# L_SaturationMeter.net
KiCad netlist of a schematic drawn in EAGLE
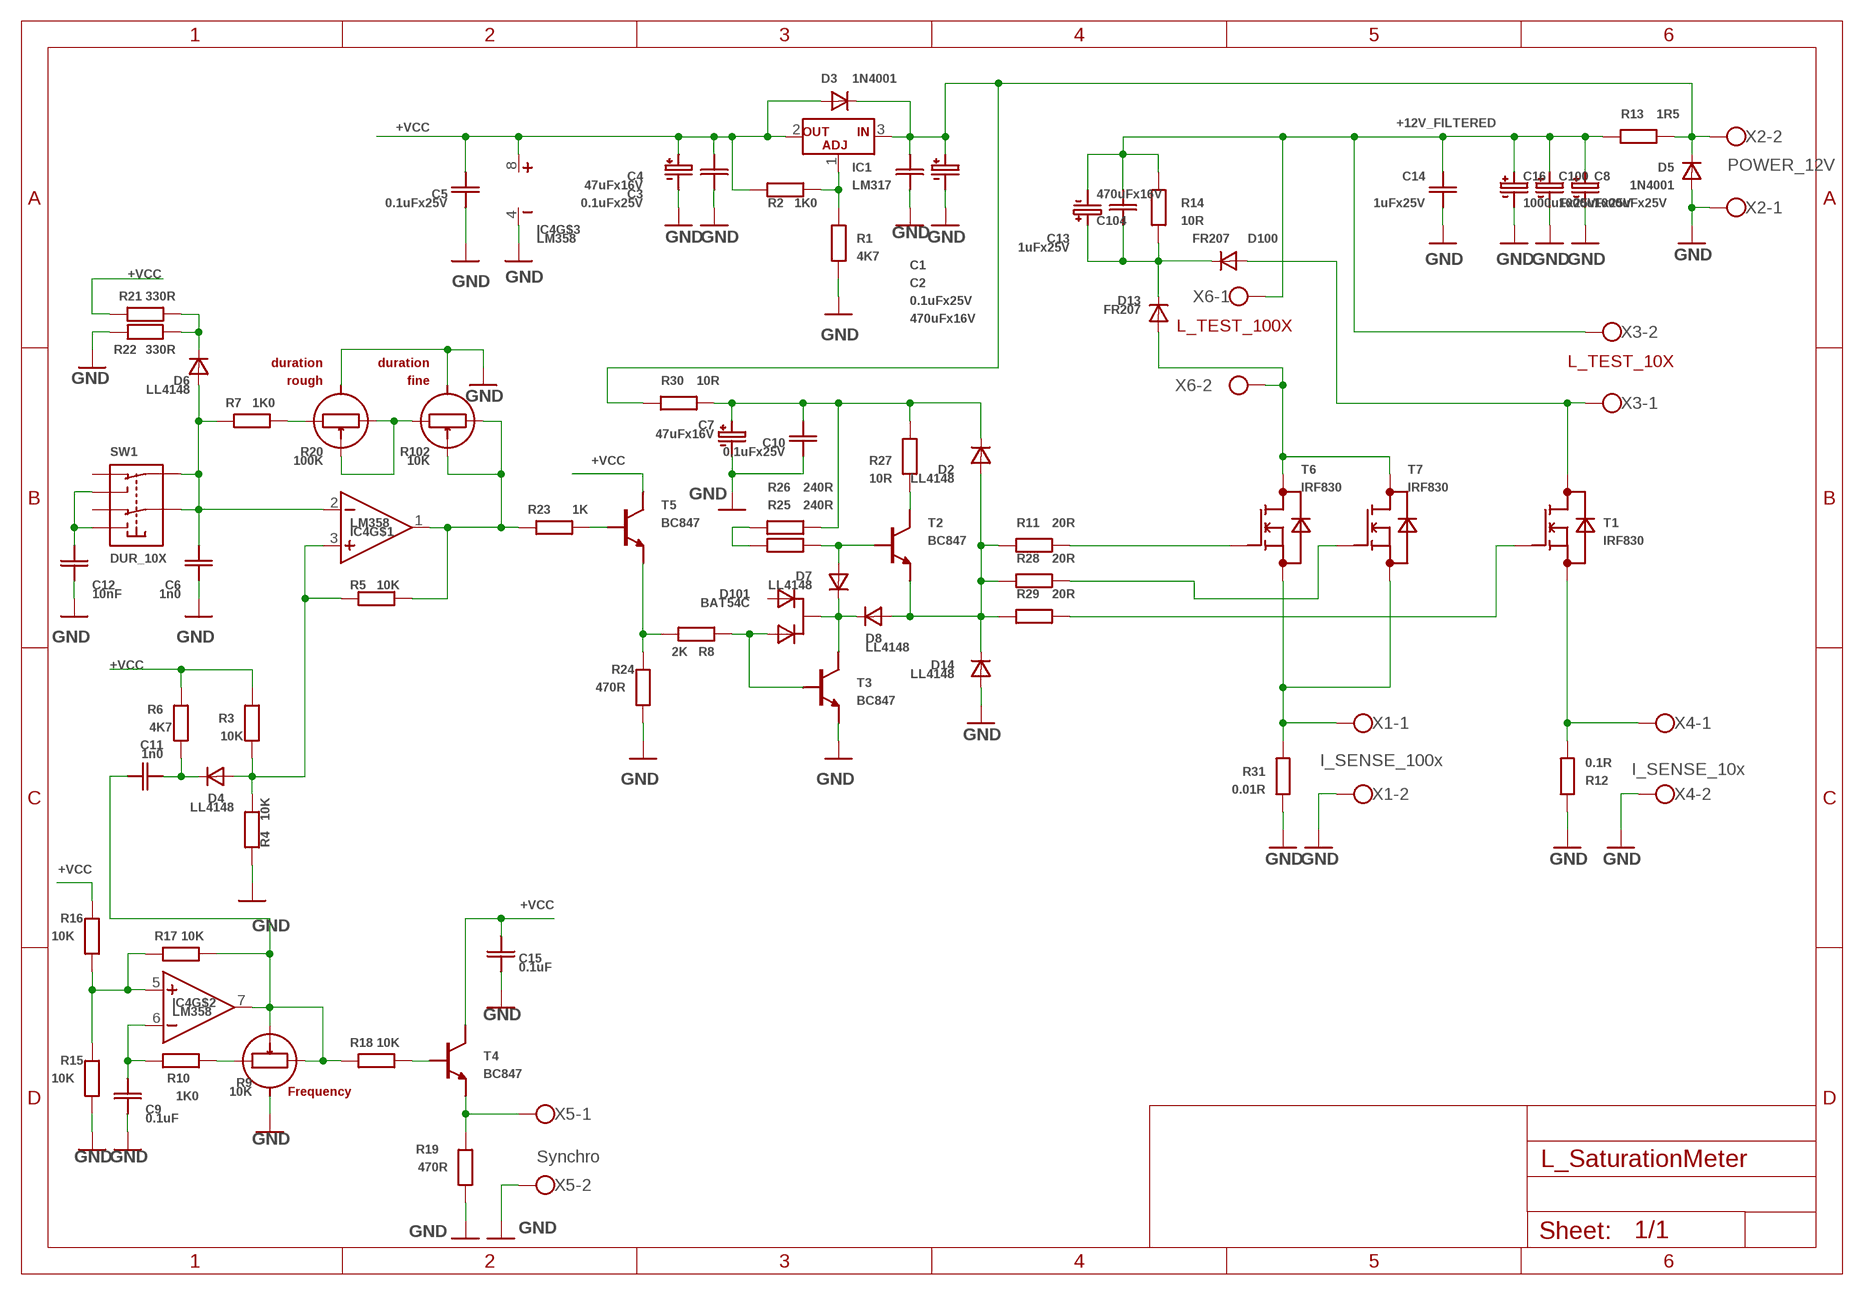
[diagram p0: schematic, sheet 1]

(export (version "E")
  (design (tool "Eeschema 10.0.6"))
  (components
    (comp (ref "C1")
      (value "0.1uFx25V")
      (footprint "eagle-import:RSMD_1206_BIG_GAP")
      (libsource (lib "eagle-import") (part "CSMD_1206_BIG_GAP"))
    )
    (comp (ref "C2")
      (value "470uFx16V")
      (footprint "eagle-import:CE_8.2MM")
      (libsource (lib "eagle-import") (part "CE8.2MM"))
    )
    (comp (ref "C3")
      (value "0.1uFx25V")
      (footprint "eagle-import:RSMD_0805")
      (libsource (lib "eagle-import") (part "CSMD_0805"))
    )
    (comp (ref "C4")
      (value "47uFx16V")
      (footprint "eagle-import:CE_5.2MM")
      (libsource (lib "eagle-import") (part "CE5.2MM"))
    )
    (comp (ref "C5")
      (value "0.1uFx25V")
      (footprint "eagle-import:RSMD_0805")
      (libsource (lib "eagle-import") (part "CSMD_0805"))
    )
    (comp (ref "C6")
      (value "1n0")
      (footprint "eagle-import:RSMD_0805")
      (libsource (lib "eagle-import") (part "CSMD_0805"))
    )
    (comp (ref "C7")
      (value "47uFx16V")
      (footprint "eagle-import:CE_5.2MM")
      (libsource (lib "eagle-import") (part "CE5.2MM"))
    )
    (comp (ref "C8")
      (value "1000uFx25V")
      (footprint "eagle-import:CE_10MM")
      (libsource (lib "eagle-import") (part "CE10MM"))
    )
    (comp (ref "C9")
      (value "0.1uF")
      (footprint "eagle-import:RSMD_0805")
      (libsource (lib "eagle-import") (part "CSMD_0805"))
    )
    (comp (ref "C10")
      (value "0.1uFx25V")
      (footprint "eagle-import:RSMD_0805")
      (libsource (lib "eagle-import") (part "CSMD_0805"))
    )
    (comp (ref "C11")
      (value "1n0")
      (footprint "eagle-import:RSMD_0805")
      (libsource (lib "eagle-import") (part "CSMD_0805"))
    )
    (comp (ref "C12")
      (value "10nF")
      (footprint "eagle-import:RSMD_0805")
      (libsource (lib "eagle-import") (part "CSMD_0805"))
    )
    (comp (ref "C13")
      (value "1uFx25V")
      (footprint "eagle-import:RSMD_1206_BIG_GAP")
      (libsource (lib "eagle-import") (part "CSMD_1206_BIG_GAP"))
    )
    (comp (ref "C14")
      (value "1uFx25V")
      (footprint "eagle-import:RSMD_1206_BIG_GAP")
      (libsource (lib "eagle-import") (part "CSMD_1206_BIG_GAP"))
    )
    (comp (ref "C15")
      (value "0.1uF")
      (footprint "eagle-import:RSMD_0805")
      (libsource (lib "eagle-import") (part "CSMD_0805"))
    )
    (comp (ref "C16")
      (value "1000uFx25V")
      (footprint "eagle-import:CE_10MM")
      (libsource (lib "eagle-import") (part "CE10MM"))
    )
    (comp (ref "C100")
      (value "1000uFx25V")
      (footprint "eagle-import:CE_10MM")
      (libsource (lib "eagle-import") (part "CE10MM"))
    )
    (comp (ref "C104")
      (value "470uFx16V")
      (footprint "eagle-import:CE_8.2MM")
      (libsource (lib "eagle-import") (part "CE8.2MM"))
    )
    (comp (ref "D2")
      (value "LL4148")
      (footprint "eagle-import:SOD-80")
      (libsource (lib "eagle-import") (part "LL4147SOD-80"))
    )
    (comp (ref "D3")
      (value "1N4001")
      (footprint "eagle-import:DO-41_15MM")
      (libsource (lib "eagle-import") (part "1N4001DO-41_15MM"))
    )
    (comp (ref "D4")
      (value "LL4148")
      (footprint "eagle-import:SOD-80")
      (libsource (lib "eagle-import") (part "LL4147SOD-80"))
    )
    (comp (ref "D5")
      (value "1N4001")
      (footprint "eagle-import:DO-41_15MM")
      (libsource (lib "eagle-import") (part "1N4001DO-41_15MM"))
    )
    (comp (ref "D6")
      (value "LL4148")
      (footprint "eagle-import:SOD-80")
      (libsource (lib "eagle-import") (part "LL4147SOD-80"))
    )
    (comp (ref "D7")
      (value "LL4148")
      (footprint "eagle-import:SOD-80")
      (libsource (lib "eagle-import") (part "LL4147SOD-80"))
    )
    (comp (ref "D8")
      (value "LL4148")
      (footprint "eagle-import:SOD-80")
      (libsource (lib "eagle-import") (part "LL4147SOD-80"))
    )
    (comp (ref "D13")
      (value "FR207")
      (footprint "eagle-import:DO-41_5MM")
      (libsource (lib "eagle-import") (part "1N4001DO-41_5MM"))
    )
    (comp (ref "D14")
      (value "LL4148")
      (footprint "eagle-import:SOD-80")
      (libsource (lib "eagle-import") (part "LL4147SOD-80"))
    )
    (comp (ref "D100")
      (value "FR207")
      (footprint "eagle-import:DO-41_20MM")
      (libsource (lib "eagle-import") (part "1N4001DO-41_20MM"))
    )
    (comp (ref "D101")
      (value "BAT54C")
      (footprint "eagle-import:SOT23_SMALL_PADS")
      (libsource (lib "eagle-import") (part "BAT54C(SOT23)"))
    )
    (comp (ref "IC1")
      (value "LM317")
      (footprint "eagle-import:D2PAK")
      (libsource (lib "eagle-import") (part "LM317(D2PAK)"))
    )
    (comp (ref "IC4")
      (value "LM358")
      (footprint "eagle-import:DIP8")
      (libsource (lib "eagle-import") (part "LM358DIP8"))
    )
    (comp (ref "R1")
      (value "4K7")
      (footprint "eagle-import:RSMD_0805")
      (libsource (lib "eagle-import") (part "RSMD_0805"))
    )
    (comp (ref "R2")
      (value "1K0")
      (footprint "eagle-import:RSMD_0805")
      (libsource (lib "eagle-import") (part "RSMD_0805"))
    )
    (comp (ref "R3")
      (value "10K")
      (footprint "eagle-import:RSMD_0805")
      (libsource (lib "eagle-import") (part "RSMD_0805"))
    )
    (comp (ref "R4")
      (value "10K")
      (footprint "eagle-import:RSMD_0805")
      (libsource (lib "eagle-import") (part "RSMD_0805"))
    )
    (comp (ref "R5")
      (value "10K")
      (footprint "eagle-import:RSMD_0805")
      (libsource (lib "eagle-import") (part "RSMD_0805"))
    )
    (comp (ref "R6")
      (value "4K7")
      (footprint "eagle-import:RSMD_0805")
      (libsource (lib "eagle-import") (part "RSMD_0805"))
    )
    (comp (ref "R7")
      (value "1K0")
      (footprint "eagle-import:RSMD_0805")
      (libsource (lib "eagle-import") (part "RSMD_0805"))
    )
    (comp (ref "R8")
      (value "2K")
      (footprint "eagle-import:RSMD_0805")
      (libsource (lib "eagle-import") (part "RSMD_0805"))
    )
    (comp (ref "R9")
      (value "10K")
      (footprint "eagle-import:SP3-4AM")
      (libsource (lib "eagle-import") (part "R_ADJ_WITH_SHIELDSP4-AM"))
    )
    (comp (ref "R10")
      (value "1K0")
      (footprint "eagle-import:RSMD_0805")
      (libsource (lib "eagle-import") (part "RSMD_0805"))
    )
    (comp (ref "R11")
      (value "20R")
      (footprint "eagle-import:RSMD_0805")
      (libsource (lib "eagle-import") (part "RSMD_0805"))
    )
    (comp (ref "R12")
      (value "0.1R")
      (footprint "eagle-import:R_1.0W_VERTICAL")
      (libsource (lib "eagle-import") (part "R1.0W_VERT"))
    )
    (comp (ref "R13")
      (value "1R5")
      (footprint "eagle-import:R_2.0W")
      (libsource (lib "eagle-import") (part "R2.0W"))
    )
    (comp (ref "R14")
      (value "10R")
      (footprint "eagle-import:R_1.0W_VERTICAL")
      (libsource (lib "eagle-import") (part "R1.0W_VERT"))
    )
    (comp (ref "R15")
      (value "10K")
      (footprint "eagle-import:RSMD_0805")
      (libsource (lib "eagle-import") (part "RSMD_0805"))
    )
    (comp (ref "R16")
      (value "10K")
      (footprint "eagle-import:RSMD_0805")
      (libsource (lib "eagle-import") (part "RSMD_0805"))
    )
    (comp (ref "R17")
      (value "10K")
      (footprint "eagle-import:RSMD_0805")
      (libsource (lib "eagle-import") (part "RSMD_0805"))
    )
    (comp (ref "R18")
      (value "10K")
      (footprint "eagle-import:RSMD_0805")
      (libsource (lib "eagle-import") (part "RSMD_0805"))
    )
    (comp (ref "R19")
      (value "470R")
      (footprint "eagle-import:RSMD_1206_BIG_GAP")
      (libsource (lib "eagle-import") (part "RSMD_1206_BIG_GAP"))
    )
    (comp (ref "R20")
      (value "100K")
      (footprint "eagle-import:SP3-4AM")
      (libsource (lib "eagle-import") (part "R_ADJ_WITH_SHIELDSP4-AM"))
    )
    (comp (ref "R21")
      (value "330R")
      (footprint "eagle-import:RSMD_0805")
      (libsource (lib "eagle-import") (part "RSMD_0805"))
    )
    (comp (ref "R22")
      (value "330R")
      (footprint "eagle-import:RSMD_0805")
      (libsource (lib "eagle-import") (part "RSMD_0805"))
    )
    (comp (ref "R23")
      (value "1K")
      (footprint "eagle-import:RSMD_1206_BIG_GAP")
      (libsource (lib "eagle-import") (part "RSMD_1206_BIG_GAP"))
    )
    (comp (ref "R24")
      (value "470R")
      (footprint "eagle-import:RSMD_1206_BIG_GAP")
      (libsource (lib "eagle-import") (part "RSMD_1206_BIG_GAP"))
    )
    (comp (ref "R25")
      (value "240R")
      (footprint "eagle-import:RSMD_1206_BIG_GAP")
      (libsource (lib "eagle-import") (part "RSMD_1206_BIG_GAP"))
    )
    (comp (ref "R26")
      (value "240R")
      (footprint "eagle-import:RSMD_1206_BIG_GAP")
      (libsource (lib "eagle-import") (part "RSMD_1206_BIG_GAP"))
    )
    (comp (ref "R27")
      (value "10R")
      (footprint "eagle-import:RSMD_1206_BIG_GAP")
      (libsource (lib "eagle-import") (part "RSMD_1206_BIG_GAP"))
    )
    (comp (ref "R28")
      (value "20R")
      (footprint "eagle-import:RSMD_0805")
      (libsource (lib "eagle-import") (part "RSMD_0805"))
    )
    (comp (ref "R29")
      (value "20R")
      (footprint "eagle-import:RSMD_0805")
      (libsource (lib "eagle-import") (part "RSMD_0805"))
    )
    (comp (ref "R30")
      (value "10R")
      (footprint "eagle-import:R_0.5W")
      (libsource (lib "eagle-import") (part "R0.5W"))
    )
    (comp (ref "R31")
      (value "0.01R")
      (footprint "eagle-import:RSMD_2512")
      (libsource (lib "eagle-import") (part "RSMD_2512"))
    )
    (comp (ref "R102")
      (value "10K")
      (footprint "eagle-import:SP3-4AM")
      (libsource (lib "eagle-import") (part "R_ADJ_WITH_SHIELDSP4-AM"))
    )
    (comp (ref "SW1")
      (value "DUR_10X")
      (footprint "eagle-import:SWITCH_DOUBLE_2.54X4.0MM")
      (libsource (lib "eagle-import") (part "SWITCH_DOUBLE(2.54X4MM)"))
    )
    (comp (ref "T1")
      (value "IRF830")
      (footprint "eagle-import:D2PAK")
      (libsource (lib "eagle-import") (part "IRF830D2PAK"))
    )
    (comp (ref "T2")
      (value "BC847")
      (footprint "eagle-import:SOT23_SMALL_PADS")
      (libsource (lib "eagle-import") (part "BC847SOT23_SMALL_PADS"))
    )
    (comp (ref "T3")
      (value "BC847")
      (footprint "eagle-import:SOT23_SMALL_PADS")
      (libsource (lib "eagle-import") (part "BC847SOT23_SMALL_PADS"))
    )
    (comp (ref "T4")
      (value "BC847")
      (footprint "eagle-import:SOT23_SMALL_PADS")
      (libsource (lib "eagle-import") (part "BC847SOT23_SMALL_PADS"))
    )
    (comp (ref "T5")
      (value "BC847")
      (footprint "eagle-import:SOT23_SMALL_PADS")
      (libsource (lib "eagle-import") (part "BC847SOT23_SMALL_PADS"))
    )
    (comp (ref "T6")
      (value "IRF830")
      (footprint "eagle-import:D2PAK")
      (libsource (lib "eagle-import") (part "IRF830D2PAK"))
    )
    (comp (ref "T7")
      (value "IRF830")
      (footprint "eagle-import:D2PAK")
      (libsource (lib "eagle-import") (part "IRF830D2PAK"))
    )
    (comp (ref "X1")
      (value "I_SENSE_100x")
      (footprint "eagle-import:W237-102")
      (fields
        (field (name "MPN") "237-102")
        (field (name "MPN_1") "237-102")
        (field (name "OC_FARNELL") "unknown")
        (field (name "OC_NEWARK") "70K9898")
      )
      (libsource (lib "eagle-import") (part "W237-102"))
    )
    (comp (ref "X2")
      (value "POWER_12V")
      (footprint "eagle-import:W237-102")
      (fields (field (name "MPN") "237-102"))
      (libsource (lib "eagle-import") (part "W237-102"))
    )
    (comp (ref "X3")
      (value "L_TEST_END")
      (footprint "eagle-import:W237-102")
      (fields (field (name "MPN") "237-102"))
      (libsource (lib "eagle-import") (part "W237-102"))
    )
    (comp (ref "X4")
      (value "I_SENSE_10x")
      (footprint "eagle-import:W237-102")
      (fields (field (name "MPN") "237-102"))
      (libsource (lib "eagle-import") (part "W237-102"))
    )
    (comp (ref "X5")
      (value "Synchro")
      (footprint "eagle-import:W237-102")
      (fields
        (field (name "MPN") "237-102")
        (field (name "MPN_1") "237-102")
        (field (name "OC_FARNELL") "unknown")
        (field (name "OC_NEWARK") "70K9898")
      )
      (libsource (lib "eagle-import") (part "W237-102"))
    )
    (comp (ref "X6")
      (value "L_TEST_END")
      (footprint "eagle-import:W237-102")
      (fields
        (field (name "MPN") "237-102")
        (field (name "MPN_1") "237-102")
        (field (name "OC_FARNELL") "unknown")
        (field (name "OC_NEWARK") "70K9898")
      )
      (libsource (lib "eagle-import") (part "W237-102"))
    )
  )
  (nets
    (net (code "1") (name "/+12V_FILTERED") (class "Default")
      (node (ref "C100") (pin "PLUS") (pinfunction "PLUS_PLUS") (pintype "bidirectional"))
      (node (ref "C104") (pin "MINUS") (pinfunction "MINUS_MINUS") (pintype "bidirectional"))
      (node (ref "C13") (pin "PAD_0") (pinfunction "PIN0_PAD_0") (pintype "bidirectional"))
      (node (ref "C14") (pin "PAD_0") (pinfunction "PIN0_PAD_0") (pintype "bidirectional"))
      (node (ref "C16") (pin "PLUS") (pinfunction "PLUS_PLUS") (pintype "bidirectional"))
      (node (ref "C8") (pin "PLUS") (pinfunction "PLUS_PLUS") (pintype "bidirectional"))
      (node (ref "R13") (pin "PAD1") (pinfunction "PIN1_PAD1") (pintype "passive"))
      (node (ref "R14") (pin "PAD1") (pinfunction "PIN1_PAD1") (pintype "passive"))
      (node (ref "X3") (pin "2") (pinfunction "KL_2") (pintype "passive"))
      (node (ref "X6") (pin "1") (pinfunction "KL_1") (pintype "passive"))
    )
    (net (code "2") (name "/+VCC") (class "Default")
      (node (ref "C15") (pin "PAD_0") (pinfunction "PIN0_PAD_0") (pintype "bidirectional"))
      (node (ref "C3") (pin "PAD_0") (pinfunction "PIN0_PAD_0") (pintype "bidirectional"))
      (node (ref "C4") (pin "PLUS") (pinfunction "PLUS_PLUS") (pintype "bidirectional"))
      (node (ref "C5") (pin "PAD_0") (pinfunction "PIN0_PAD_0") (pintype "bidirectional"))
      (node (ref "D3") (pin "ANODE") (pinfunction "ANODE_ANODE") (pintype "passive"))
      (node (ref "IC1") (pin "2") (pinfunction "OUT_2") (pintype "output"))
      (node (ref "IC4") (pin "8") (pinfunction "VCC_8") (pintype "power_in"))
      (node (ref "R16") (pin "PAD_1") (pinfunction "PIN1_PAD_1") (pintype "passive"))
      (node (ref "R2") (pin "PAD_1") (pinfunction "PIN1_PAD_1") (pintype "passive"))
      (node (ref "R21") (pin "PAD_1") (pinfunction "PIN1_PAD_1") (pintype "passive"))
      (node (ref "R3") (pin "PAD_1") (pinfunction "PIN1_PAD_1") (pintype "passive"))
      (node (ref "R6") (pin "PAD_0") (pinfunction "PIN0_PAD_0") (pintype "passive"))
      (node (ref "T4") (pin "3") (pinfunction "C_3") (pintype "bidirectional"))
      (node (ref "T5") (pin "3") (pinfunction "C_3") (pintype "bidirectional"))
    )
    (net (code "3") (name "GND") (class "Default")
      (node (ref "C1") (pin "PAD_1") (pinfunction "PIN1_PAD_1") (pintype "bidirectional"))
      (node (ref "C10") (pin "PAD_1") (pinfunction "PIN1_PAD_1") (pintype "bidirectional"))
      (node (ref "C100") (pin "MINUS") (pinfunction "MINUS_MINUS") (pintype "bidirectional"))
      (node (ref "C12") (pin "PAD_1") (pinfunction "PIN1_PAD_1") (pintype "bidirectional"))
      (node (ref "C14") (pin "PAD_1") (pinfunction "PIN1_PAD_1") (pintype "bidirectional"))
      (node (ref "C15") (pin "PAD_1") (pinfunction "PIN1_PAD_1") (pintype "bidirectional"))
      (node (ref "C16") (pin "MINUS") (pinfunction "MINUS_MINUS") (pintype "bidirectional"))
      (node (ref "C2") (pin "MINUS") (pinfunction "MINUS_MINUS") (pintype "bidirectional"))
      (node (ref "C3") (pin "PAD_1") (pinfunction "PIN1_PAD_1") (pintype "bidirectional"))
      (node (ref "C4") (pin "MINUS") (pinfunction "MINUS_MINUS") (pintype "bidirectional"))
      (node (ref "C5") (pin "PAD_1") (pinfunction "PIN1_PAD_1") (pintype "bidirectional"))
      (node (ref "C6") (pin "PAD_1") (pinfunction "PIN1_PAD_1") (pintype "bidirectional"))
      (node (ref "C7") (pin "MINUS") (pinfunction "MINUS_MINUS") (pintype "bidirectional"))
      (node (ref "C8") (pin "MINUS") (pinfunction "MINUS_MINUS") (pintype "bidirectional"))
      (node (ref "C9") (pin "PAD_1") (pinfunction "PIN1_PAD_1") (pintype "bidirectional"))
      (node (ref "D14") (pin "ANODE") (pinfunction "ANODE_ANODE") (pintype "passive"))
      (node (ref "D5") (pin "ANODE") (pinfunction "ANODE_ANODE") (pintype "passive"))
      (node (ref "IC4") (pin "4") (pinfunction "GND_4") (pintype "power_in"))
      (node (ref "R1") (pin "PAD_0") (pinfunction "PIN0_PAD_0") (pintype "passive"))
      (node (ref "R102") (pin "PACKAGE1") (pinfunction "PACKAGE_PACKAGE1") (pintype "bidirectional"))
      (node (ref "R102") (pin "PACKAGE2") (pinfunction "PACKAGE_PACKAGE2") (pintype "bidirectional"))
      (node (ref "R12") (pin "PAD1") (pinfunction "PIN1_PAD1") (pintype "passive"))
      (node (ref "R15") (pin "PAD_0") (pinfunction "PIN0_PAD_0") (pintype "passive"))
      (node (ref "R19") (pin "PAD_1") (pinfunction "PIN1_PAD_1") (pintype "passive"))
      (node (ref "R20") (pin "PACKAGE1") (pinfunction "PACKAGE_PACKAGE1") (pintype "bidirectional"))
      (node (ref "R20") (pin "PACKAGE2") (pinfunction "PACKAGE_PACKAGE2") (pintype "bidirectional"))
      (node (ref "R22") (pin "PAD_0") (pinfunction "PIN0_PAD_0") (pintype "passive"))
      (node (ref "R24") (pin "PAD_1") (pinfunction "PIN1_PAD_1") (pintype "passive"))
      (node (ref "R31") (pin "PAD0") (pinfunction "PIN0_PAD0") (pintype "passive"))
      (node (ref "R4") (pin "PAD_1") (pinfunction "PIN1_PAD_1") (pintype "passive"))
      (node (ref "R9") (pin "PACKAGE1") (pinfunction "PACKAGE_PACKAGE1") (pintype "bidirectional"))
      (node (ref "R9") (pin "PACKAGE2") (pinfunction "PACKAGE_PACKAGE2") (pintype "bidirectional"))
      (node (ref "T3") (pin "2") (pinfunction "E_2") (pintype "bidirectional"))
      (node (ref "X1") (pin "2") (pinfunction "KL_2") (pintype "passive"))
      (node (ref "X2") (pin "1") (pinfunction "KL_1") (pintype "passive"))
      (node (ref "X4") (pin "2") (pinfunction "KL_2") (pintype "passive"))
      (node (ref "X5") (pin "2") (pinfunction "KL_2") (pintype "passive"))
    )
    (net (code "4") (name "Net-(C1-PIN0)") (class "Default")
      (node (ref "C1") (pin "PAD_0") (pinfunction "PIN0_PAD_0") (pintype "bidirectional"))
      (node (ref "C2") (pin "PLUS") (pinfunction "PLUS_PLUS") (pintype "bidirectional"))
      (node (ref "D3") (pin "CATHODE") (pinfunction "CATHODE_CATHODE") (pintype "passive"))
      (node (ref "D5") (pin "CATHODE") (pinfunction "CATHODE_CATHODE") (pintype "passive"))
      (node (ref "IC1") (pin "3") (pinfunction "IN_3") (pintype "input"))
      (node (ref "R13") (pin "PAD_0") (pinfunction "PIN0_PAD_0") (pintype "passive"))
      (node (ref "R30") (pin "PAD1") (pinfunction "PIN1_PAD1") (pintype "passive"))
      (node (ref "X2") (pin "2") (pinfunction "KL_2") (pintype "passive"))
    )
    (net (code "5") (name "Net-(C6-PIN0)") (class "Default")
      (node (ref "C6") (pin "PAD_0") (pinfunction "PIN0_PAD_0") (pintype "bidirectional"))
      (node (ref "D6") (pin "ANODE") (pinfunction "ANODE_ANODE") (pintype "passive"))
      (node (ref "IC4") (pin "2") (pinfunction "IN-_2") (pintype "input"))
      (node (ref "R7") (pin "PAD_1") (pinfunction "PIN1_PAD_1") (pintype "passive"))
      (node (ref "SW1") (pin "CENTER1") (pinfunction "CENTER1_CENTER1") (pintype "bidirectional"))
      (node (ref "SW1") (pin "CENTER2") (pinfunction "CENTER2_CENTER2") (pintype "bidirectional"))
    )
    (net (code "6") (name "Net-(C9-PIN0)") (class "Default")
      (node (ref "C9") (pin "PAD_0") (pinfunction "PIN0_PAD_0") (pintype "bidirectional"))
      (node (ref "IC4") (pin "6") (pinfunction "IN-_6") (pintype "input"))
      (node (ref "R10") (pin "PAD_0") (pinfunction "PIN0_PAD_0") (pintype "passive"))
    )
    (net (code "7") (name "Net-(C10-PIN0)") (class "Default")
      (node (ref "C10") (pin "PAD_0") (pinfunction "PIN0_PAD_0") (pintype "bidirectional"))
      (node (ref "C7") (pin "PLUS") (pinfunction "PLUS_PLUS") (pintype "bidirectional"))
      (node (ref "D2") (pin "CATHODE") (pinfunction "CATHODE_CATHODE") (pintype "passive"))
      (node (ref "R26") (pin "PAD_0") (pinfunction "PIN0_PAD_0") (pintype "passive"))
      (node (ref "R27") (pin "PAD_0") (pinfunction "PIN0_PAD_0") (pintype "passive"))
      (node (ref "R30") (pin "PAD_0") (pinfunction "PIN0_PAD_0") (pintype "passive"))
    )
    (net (code "8") (name "Net-(C11-PIN0)") (class "Default")
      (node (ref "C11") (pin "PAD_0") (pinfunction "PIN0_PAD_0") (pintype "bidirectional"))
      (node (ref "D4") (pin "CATHODE") (pinfunction "CATHODE_CATHODE") (pintype "passive"))
      (node (ref "R6") (pin "PAD_1") (pinfunction "PIN1_PAD_1") (pintype "passive"))
    )
    (net (code "9") (name "Net-(C11-PIN1)") (class "Default")
      (node (ref "C11") (pin "PAD_1") (pinfunction "PIN1_PAD_1") (pintype "bidirectional"))
      (node (ref "IC4") (pin "7") (pinfunction "OUT_7") (pintype "output"))
      (node (ref "R17") (pin "PAD_0") (pinfunction "PIN0_PAD_0") (pintype "passive"))
      (node (ref "R18") (pin "PAD_1") (pinfunction "PIN1_PAD_1") (pintype "passive"))
      (node (ref "R9") (pin "END_B") (pinfunction "END_B_END_B") (pintype "passive"))
      (node (ref "R9") (pin "MIDDLE") (pinfunction "MIDDLE_MIDDLE") (pintype "passive"))
    )
    (net (code "10") (name "Net-(C12-PIN0)") (class "Default")
      (node (ref "C12") (pin "PAD_0") (pinfunction "PIN0_PAD_0") (pintype "bidirectional"))
      (node (ref "SW1") (pin "POS_A1") (pinfunction "POS_A1_POS_A1") (pintype "bidirectional"))
      (node (ref "SW1") (pin "POS_A2") (pinfunction "POS_A2_POS_A2") (pintype "bidirectional"))
    )
    (net (code "11") (name "Net-(C13-PIN1)") (class "Default")
      (node (ref "C104") (pin "PLUS") (pinfunction "PLUS_PLUS") (pintype "bidirectional"))
      (node (ref "C13") (pin "PAD_1") (pinfunction "PIN1_PAD_1") (pintype "bidirectional"))
      (node (ref "D100") (pin "CATHODE") (pinfunction "CATHODE_CATHODE") (pintype "passive"))
      (node (ref "D13") (pin "CATHODE") (pinfunction "CATHODE_CATHODE") (pintype "passive"))
      (node (ref "R14") (pin "PAD_0") (pinfunction "PIN0_PAD_0") (pintype "passive"))
    )
    (net (code "12") (name "Net-(D101-ANODE2)") (class "Default")
      (node (ref "D101") (pin "2") (pinfunction "ANODE2_2") (pintype "passive"))
      (node (ref "R8") (pin "PAD_1") (pinfunction "PIN1_PAD_1") (pintype "passive"))
      (node (ref "T3") (pin "1") (pinfunction "B_1") (pintype "bidirectional"))
    )
    (net (code "13") (name "Net-(D101-CATHODE)") (class "Default")
      (node (ref "D101") (pin "3") (pinfunction "CATHODE_3") (pintype "passive"))
      (node (ref "D7") (pin "CATHODE") (pinfunction "CATHODE_CATHODE") (pintype "passive"))
      (node (ref "D8") (pin "CATHODE") (pinfunction "CATHODE_CATHODE") (pintype "passive"))
      (node (ref "T3") (pin "3") (pinfunction "C_3") (pintype "bidirectional"))
    )
    (net (code "14") (name "Net-(IC1-ADJ)") (class "Default")
      (node (ref "IC1") (pin "1") (pinfunction "ADJ_1") (pintype "input"))
      (node (ref "R1") (pin "PAD_1") (pinfunction "PIN1_PAD_1") (pintype "passive"))
      (node (ref "R2") (pin "PAD_0") (pinfunction "PIN0_PAD_0") (pintype "passive"))
    )
    (net (code "15") (name "Net-(IC4A-IN+)") (class "Default")
      (node (ref "D4") (pin "ANODE") (pinfunction "ANODE_ANODE") (pintype "passive"))
      (node (ref "IC4") (pin "3") (pinfunction "IN+_3") (pintype "input"))
      (node (ref "R3") (pin "PAD_0") (pinfunction "PIN0_PAD_0") (pintype "passive"))
      (node (ref "R4") (pin "PAD_0") (pinfunction "PIN0_PAD_0") (pintype "passive"))
      (node (ref "R5") (pin "PAD_1") (pinfunction "PIN1_PAD_1") (pintype "passive"))
    )
    (net (code "16") (name "Net-(IC4A-OUT)") (class "Default")
      (node (ref "IC4") (pin "1") (pinfunction "OUT_1") (pintype "output"))
      (node (ref "R102") (pin "END_B") (pinfunction "END_B_END_B") (pintype "passive"))
      (node (ref "R102") (pin "MIDDLE") (pinfunction "MIDDLE_MIDDLE") (pintype "passive"))
      (node (ref "R23") (pin "PAD_1") (pinfunction "PIN1_PAD_1") (pintype "passive"))
      (node (ref "R5") (pin "PAD_0") (pinfunction "PIN0_PAD_0") (pintype "passive"))
    )
    (net (code "17") (name "Net-(IC4B-IN+)") (class "Default")
      (node (ref "IC4") (pin "5") (pinfunction "IN+_5") (pintype "input"))
      (node (ref "R15") (pin "PAD_1") (pinfunction "PIN1_PAD_1") (pintype "passive"))
      (node (ref "R16") (pin "PAD_0") (pinfunction "PIN0_PAD_0") (pintype "passive"))
      (node (ref "R17") (pin "PAD_1") (pinfunction "PIN1_PAD_1") (pintype "passive"))
    )
    (net (code "18") (name "Net-(R7-PIN0)") (class "Default")
      (node (ref "R20") (pin "END_A") (pinfunction "END_A_END_A") (pintype "passive"))
      (node (ref "R7") (pin "PAD_0") (pinfunction "PIN0_PAD_0") (pintype "passive"))
    )
    (net (code "19") (name "Net-(R10-PIN1)") (class "Default")
      (node (ref "R10") (pin "PAD_1") (pinfunction "PIN1_PAD_1") (pintype "passive"))
      (node (ref "R9") (pin "END_A") (pinfunction "END_A_END_A") (pintype "passive"))
    )
    (net (code "20") (name "Net-(R11-PIN0)") (class "Default")
      (node (ref "D14") (pin "CATHODE") (pinfunction "CATHODE_CATHODE") (pintype "passive"))
      (node (ref "D2") (pin "ANODE") (pinfunction "ANODE_ANODE") (pintype "passive"))
      (node (ref "D8") (pin "ANODE") (pinfunction "ANODE_ANODE") (pintype "passive"))
      (node (ref "R11") (pin "PAD_0") (pinfunction "PIN0_PAD_0") (pintype "passive"))
      (node (ref "R28") (pin "PAD_0") (pinfunction "PIN0_PAD_0") (pintype "passive"))
      (node (ref "R29") (pin "PAD_0") (pinfunction "PIN0_PAD_0") (pintype "passive"))
      (node (ref "T2") (pin "2") (pinfunction "E_2") (pintype "bidirectional"))
    )
    (net (code "21") (name "Net-(R11-PIN1)") (class "Default")
      (node (ref "R11") (pin "PAD_1") (pinfunction "PIN1_PAD_1") (pintype "passive"))
      (node (ref "T6") (pin "1") (pinfunction "GATE_1") (pintype "bidirectional"))
    )
    (net (code "22") (name "Net-(R12-PIN0)") (class "Default")
      (node (ref "R12") (pin "PAD_0") (pinfunction "PIN0_PAD_0") (pintype "passive"))
      (node (ref "T1") (pin "3") (pinfunction "SOURCE_3") (pintype "bidirectional"))
      (node (ref "X4") (pin "1") (pinfunction "KL_1") (pintype "passive"))
    )
    (net (code "23") (name "Net-(R18-PIN0)") (class "Default")
      (node (ref "R18") (pin "PAD_0") (pinfunction "PIN0_PAD_0") (pintype "passive"))
      (node (ref "T4") (pin "1") (pinfunction "B_1") (pintype "bidirectional"))
    )
    (net (code "24") (name "Net-(R19-PIN0)") (class "Default")
      (node (ref "R19") (pin "PAD_0") (pinfunction "PIN0_PAD_0") (pintype "passive"))
      (node (ref "T4") (pin "2") (pinfunction "E_2") (pintype "bidirectional"))
      (node (ref "X5") (pin "1") (pinfunction "KL_1") (pintype "passive"))
    )
    (net (code "25") (name "Net-(R21-PIN0)") (class "Default")
      (node (ref "D6") (pin "CATHODE") (pinfunction "CATHODE_CATHODE") (pintype "passive"))
      (node (ref "R21") (pin "PAD_0") (pinfunction "PIN0_PAD_0") (pintype "passive"))
      (node (ref "R22") (pin "PAD_1") (pinfunction "PIN1_PAD_1") (pintype "passive"))
    )
    (net (code "26") (name "Net-(R23-PIN0)") (class "Default")
      (node (ref "R23") (pin "PAD_0") (pinfunction "PIN0_PAD_0") (pintype "passive"))
      (node (ref "T5") (pin "1") (pinfunction "B_1") (pintype "bidirectional"))
    )
    (net (code "27") (name "Net-(R24-PIN0)") (class "Default")
      (node (ref "R24") (pin "PAD_0") (pinfunction "PIN0_PAD_0") (pintype "passive"))
      (node (ref "R8") (pin "PAD_0") (pinfunction "PIN0_PAD_0") (pintype "passive"))
      (node (ref "T5") (pin "2") (pinfunction "E_2") (pintype "bidirectional"))
    )
    (net (code "28") (name "Net-(R25-PIN0)") (class "Default")
      (node (ref "R25") (pin "PAD_0") (pinfunction "PIN0_PAD_0") (pintype "passive"))
      (node (ref "R26") (pin "PAD_1") (pinfunction "PIN1_PAD_1") (pintype "passive"))
    )
    (net (code "29") (name "Net-(R25-PIN1)") (class "Default")
      (node (ref "D7") (pin "ANODE") (pinfunction "ANODE_ANODE") (pintype "passive"))
      (node (ref "R25") (pin "PAD_1") (pinfunction "PIN1_PAD_1") (pintype "passive"))
      (node (ref "T2") (pin "1") (pinfunction "B_1") (pintype "bidirectional"))
    )
    (net (code "30") (name "Net-(R27-PIN1)") (class "Default")
      (node (ref "R27") (pin "PAD_1") (pinfunction "PIN1_PAD_1") (pintype "passive"))
      (node (ref "T2") (pin "3") (pinfunction "C_3") (pintype "bidirectional"))
    )
    (net (code "31") (name "Net-(R28-PIN1)") (class "Default")
      (node (ref "R28") (pin "PAD_1") (pinfunction "PIN1_PAD_1") (pintype "passive"))
      (node (ref "T7") (pin "1") (pinfunction "GATE_1") (pintype "bidirectional"))
    )
    (net (code "32") (name "Net-(R29-PIN1)") (class "Default")
      (node (ref "R29") (pin "PAD_1") (pinfunction "PIN1_PAD_1") (pintype "passive"))
      (node (ref "T1") (pin "1") (pinfunction "GATE_1") (pintype "bidirectional"))
    )
    (net (code "33") (name "Net-(R31-PIN1)") (class "Default")
      (node (ref "R31") (pin "PAD1") (pinfunction "PIN1_PAD1") (pintype "passive"))
      (node (ref "T6") (pin "3") (pinfunction "SOURCE_3") (pintype "bidirectional"))
      (node (ref "T7") (pin "3") (pinfunction "SOURCE_3") (pintype "bidirectional"))
      (node (ref "X1") (pin "1") (pinfunction "KL_1") (pintype "passive"))
    )
    (net (code "34") (name "Net-(R102-PadEND_A)") (class "Default")
      (node (ref "R102") (pin "END_A") (pinfunction "END_A_END_A") (pintype "passive"))
      (node (ref "R20") (pin "END_B") (pinfunction "END_B_END_B") (pintype "passive"))
      (node (ref "R20") (pin "MIDDLE") (pinfunction "MIDDLE_MIDDLE") (pintype "passive"))
    )
    (net (code "35") (name "Net-(T1-DRAIN)") (class "Default")
      (node (ref "D100") (pin "ANODE") (pinfunction "ANODE_ANODE") (pintype "passive"))
      (node (ref "T1") (pin "2") (pinfunction "DRAIN_2") (pintype "bidirectional"))
      (node (ref "X3") (pin "1") (pinfunction "KL_1") (pintype "passive"))
    )
    (net (code "36") (name "Net-(T6-DRAIN)") (class "Default")
      (node (ref "D13") (pin "ANODE") (pinfunction "ANODE_ANODE") (pintype "passive"))
      (node (ref "T6") (pin "2") (pinfunction "DRAIN_2") (pintype "bidirectional"))
      (node (ref "T7") (pin "2") (pinfunction "DRAIN_2") (pintype "bidirectional"))
      (node (ref "X6") (pin "2") (pinfunction "KL_2") (pintype "passive"))
    )
    (net (code "37") (name "unconnected-(D101-ANODE1-Pad1)") (class "Default")
      (node (ref "D101") (pin "1") (pinfunction "ANODE1_1") (pintype "passive"))
    )
    (net (code "38") (name "unconnected-(SW1-PadPOS_B1)") (class "Default")
      (node (ref "SW1") (pin "POS_B1") (pinfunction "POS_B1_POS_B1") (pintype "bidirectional"))
    )
    (net (code "39") (name "unconnected-(SW1-PadPOS_B2)") (class "Default")
      (node (ref "SW1") (pin "POS_B2") (pinfunction "POS_B2_POS_B2") (pintype "bidirectional"))
    )
  )
)
